# Half_Bridges.net
KiCad netlist of a schematic drawn in Altium Designer
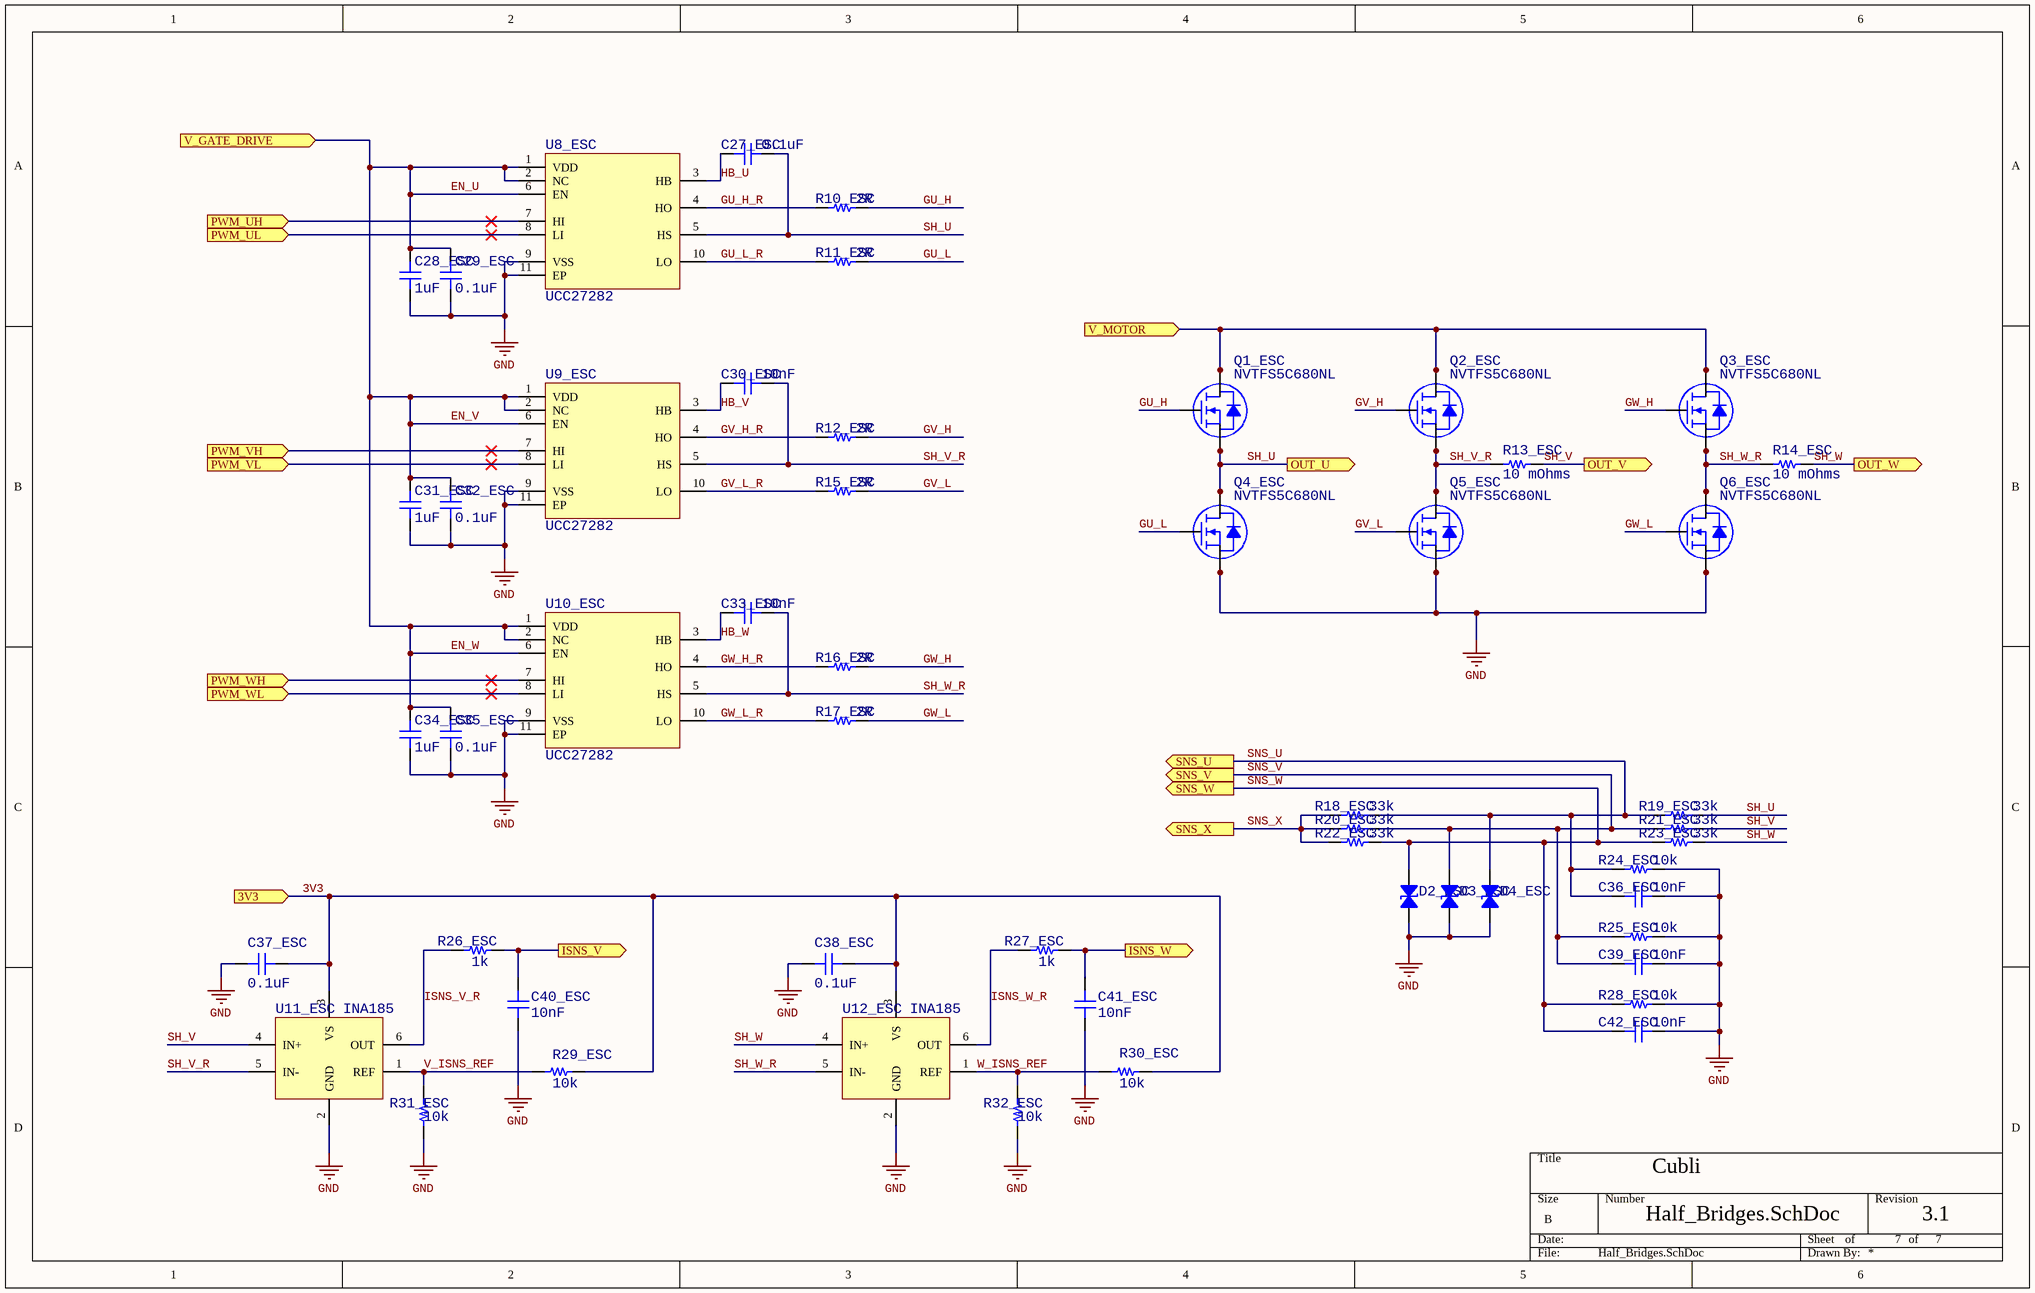
[diagram p0: Half_Bridges.SchDoc]

(export (version "E")
  (design (tool "Eeschema 10.0.6"))
  (components
    (comp (ref "C27_ESC")
      (value "0.1uF")
      (footprint "CAP_0402")
      (description "CAP CER 402")
      (libsource (lib "IC") (part "CAP_0402"))
    )
    (comp (ref "C28_ESC")
      (value "1uF")
      (footprint "CAP_0402")
      (description "CAP CER 402")
      (libsource (lib "IC") (part "CAP_0402"))
    )
    (comp (ref "C29_ESC")
      (value "0.1uF")
      (footprint "CAP_0402")
      (description "CAP CER 402")
      (libsource (lib "IC") (part "CAP_0402"))
    )
    (comp (ref "C30_ESC")
      (value "10nF")
      (footprint "CAP_0402")
      (description "CAP CER 402")
      (libsource (lib "IC") (part "CAP_0402"))
    )
    (comp (ref "C31_ESC")
      (value "1uF")
      (footprint "CAP_0402")
      (description "CAP CER 402")
      (libsource (lib "IC") (part "CAP_0402"))
    )
    (comp (ref "C32_ESC")
      (value "0.1uF")
      (footprint "CAP_0402")
      (description "CAP CER 402")
      (libsource (lib "IC") (part "CAP_0402"))
    )
    (comp (ref "C33_ESC")
      (value "10nF")
      (footprint "CAP_0402")
      (description "CAP CER 402")
      (libsource (lib "IC") (part "CAP_0402"))
    )
    (comp (ref "C34_ESC")
      (value "1uF")
      (footprint "CAP_0402")
      (description "CAP CER 402")
      (libsource (lib "IC") (part "CAP_0402"))
    )
    (comp (ref "C35_ESC")
      (value "0.1uF")
      (footprint "CAP_0402")
      (description "CAP CER 402")
      (libsource (lib "IC") (part "CAP_0402"))
    )
    (comp (ref "C36_ESC")
      (value "10nF")
      (footprint "CAP_0402")
      (description "CAP CER 402")
      (libsource (lib "IC") (part "CAP_0402"))
    )
    (comp (ref "C37_ESC")
      (value "0.1uF")
      (footprint "CAP_0402")
      (description "CAP CER 402")
      (libsource (lib "IC") (part "CAP_0402"))
    )
    (comp (ref "C38_ESC")
      (value "0.1uF")
      (footprint "CAP_0402")
      (description "CAP CER 402")
      (libsource (lib "IC") (part "CAP_0402"))
    )
    (comp (ref "C39_ESC")
      (value "10nF")
      (footprint "CAP_0402")
      (description "CAP CER 402")
      (libsource (lib "IC") (part "CAP_0402"))
    )
    (comp (ref "C40_ESC")
      (value "10nF")
      (footprint "CAP_0402")
      (description "CAP CER 402")
      (libsource (lib "IC") (part "CAP_0402"))
    )
    (comp (ref "C41_ESC")
      (value "10nF")
      (footprint "CAP_0402")
      (description "CAP CER 402")
      (libsource (lib "IC") (part "CAP_0402"))
    )
    (comp (ref "C42_ESC")
      (value "10nF")
      (footprint "CAP_0402")
      (description "CAP CER 402")
      (libsource (lib "IC") (part "CAP_0402"))
    )
    (comp (ref "D2_ESC")
      (value "TVN3V3B1S-DFN1006-2LDG")
      (footprint "0402")
      (description "TVS DIODE 3.3V 14.2PF DFN1006")
      (fields (field (name "MANUFACTURER") "INPAQ Technology Co., Ltd"))
      (libsource (lib "Celestial Altium Library - altium_library") (part "Diode TVS"))
    )
    (comp (ref "D3_ESC")
      (value "TVN3V3B1S-DFN1006-2LDG")
      (footprint "0402")
      (description "TVS DIODE 3.3V 14.2PF DFN1006")
      (fields (field (name "MANUFACTURER") "INPAQ Technology Co., Ltd"))
      (libsource (lib "Celestial Altium Library - altium_library") (part "Diode TVS"))
    )
    (comp (ref "D4_ESC")
      (value "TVN3V3B1S-DFN1006-2LDG")
      (footprint "0402")
      (description "TVS DIODE 3.3V 14.2PF DFN1006")
      (fields (field (name "MANUFACTURER") "INPAQ Technology Co., Ltd"))
      (libsource (lib "Celestial Altium Library - altium_library") (part "Diode TVS"))
    )
    (comp (ref "Q1_ESC")
      (value "NVTFS5C680NL")
      (footprint "NVTFS015N04CTAG")
      (description "N-FET")
      (libsource (lib "IC") (part "NVTFS5C680NL"))
    )
    (comp (ref "Q2_ESC")
      (value "NVTFS5C680NL")
      (footprint "NVTFS015N04CTAG")
      (description "N-FET")
      (libsource (lib "IC") (part "NVTFS5C680NL"))
    )
    (comp (ref "Q3_ESC")
      (value "NVTFS5C680NL")
      (footprint "NVTFS015N04CTAG")
      (description "N-FET")
      (libsource (lib "IC") (part "NVTFS5C680NL"))
    )
    (comp (ref "Q4_ESC")
      (value "NVTFS5C680NL")
      (footprint "NVTFS015N04CTAG")
      (description "N-FET")
      (libsource (lib "IC") (part "NVTFS5C680NL"))
    )
    (comp (ref "Q5_ESC")
      (value "NVTFS5C680NL")
      (footprint "NVTFS015N04CTAG")
      (description "N-FET")
      (libsource (lib "IC") (part "NVTFS5C680NL"))
    )
    (comp (ref "Q6_ESC")
      (value "NVTFS5C680NL")
      (footprint "NVTFS015N04CTAG")
      (description "N-FET")
      (libsource (lib "IC") (part "NVTFS5C680NL"))
    )
    (comp (ref "R10_ESC")
      (value "2R")
      (footprint "RES_0402")
      (description "RES 0402")
      (libsource (lib "IC") (part "RES_0402"))
    )
    (comp (ref "R11_ESC")
      (value "2R")
      (footprint "RES_0402")
      (description "RES 0402")
      (libsource (lib "IC") (part "RES_0402"))
    )
    (comp (ref "R12_ESC")
      (value "2R")
      (footprint "RES_0402")
      (description "RES 0402")
      (libsource (lib "IC") (part "RES_0402"))
    )
    (comp (ref "R13_ESC")
      (value "10 mOhms")
      (footprint "RES 1206_3216")
      (description "RES 0.039 OHM 1% 3/4W 1206")
      (fields (field (name "PART NUMBER") "KRL1632E-M-R039-F-T5") (field (name "MANUFACTURER") "Susumu"))
      (libsource (lib "Celestial Altium Library - altium_library") (part "Resistor"))
    )
    (comp (ref "R14_ESC")
      (value "10 mOhms")
      (footprint "RES 1206_3216")
      (description "RES 0.039 OHM 1% 3/4W 1206")
      (fields (field (name "PART NUMBER") "KRL1632E-M-R039-F-T5") (field (name "MANUFACTURER") "Susumu"))
      (libsource (lib "Celestial Altium Library - altium_library") (part "Resistor"))
    )
    (comp (ref "R15_ESC")
      (value "2R")
      (footprint "RES_0402")
      (description "RES 0402")
      (libsource (lib "IC") (part "RES_0402"))
    )
    (comp (ref "R16_ESC")
      (value "2R")
      (footprint "RES_0402")
      (description "RES 0402")
      (libsource (lib "IC") (part "RES_0402"))
    )
    (comp (ref "R17_ESC")
      (value "2R")
      (footprint "RES_0402")
      (description "RES 0402")
      (libsource (lib "IC") (part "RES_0402"))
    )
    (comp (ref "R18_ESC")
      (value "33k")
      (footprint "RES_0402")
      (description "RES 0402")
      (libsource (lib "IC") (part "RES_0402"))
    )
    (comp (ref "R19_ESC")
      (value "33k")
      (footprint "RES_0402")
      (description "RES 0402")
      (libsource (lib "IC") (part "RES_0402"))
    )
    (comp (ref "R20_ESC")
      (value "33k")
      (footprint "RES_0402")
      (description "RES 0402")
      (libsource (lib "IC") (part "RES_0402"))
    )
    (comp (ref "R21_ESC")
      (value "33k")
      (footprint "RES_0402")
      (description "RES 0402")
      (libsource (lib "IC") (part "RES_0402"))
    )
    (comp (ref "R22_ESC")
      (value "33k")
      (footprint "RES_0402")
      (description "RES 0402")
      (libsource (lib "IC") (part "RES_0402"))
    )
    (comp (ref "R23_ESC")
      (value "33k")
      (footprint "RES_0402")
      (description "RES 0402")
      (libsource (lib "IC") (part "RES_0402"))
    )
    (comp (ref "R24_ESC")
      (value "10k")
      (footprint "RES_0402")
      (description "RES 0402")
      (libsource (lib "IC") (part "RES_0402"))
    )
    (comp (ref "R25_ESC")
      (value "10k")
      (footprint "RES_0402")
      (description "RES 0402")
      (libsource (lib "IC") (part "RES_0402"))
    )
    (comp (ref "R26_ESC")
      (value "1k")
      (footprint "RES_0402")
      (description "RES 0402")
      (libsource (lib "IC") (part "RES_0402"))
    )
    (comp (ref "R27_ESC")
      (value "1k")
      (footprint "RES_0402")
      (description "RES 0402")
      (libsource (lib "IC") (part "RES_0402"))
    )
    (comp (ref "R28_ESC")
      (value "10k")
      (footprint "RES_0402")
      (description "RES 0402")
      (libsource (lib "IC") (part "RES_0402"))
    )
    (comp (ref "R29_ESC")
      (value "10k")
      (footprint "RES_0402")
      (description "RES 0402")
      (libsource (lib "IC") (part "RES_0402"))
    )
    (comp (ref "R30_ESC")
      (value "10k")
      (footprint "RES_0402")
      (description "RES 0402")
      (libsource (lib "IC") (part "RES_0402"))
    )
    (comp (ref "R31_ESC")
      (value "10k")
      (footprint "RES_0402")
      (description "RES 0402")
      (libsource (lib "IC") (part "RES_0402"))
    )
    (comp (ref "R32_ESC")
      (value "10k")
      (footprint "RES_0402")
      (description "RES 0402")
      (libsource (lib "IC") (part "RES_0402"))
    )
    (comp (ref "U8_ESC")
      (value "UCC27282")
      (footprint "VSON-10")
      (description "3-A, 120-V half bridge gate driver with 5-V UVLO, interlock and enable 10-VSON -40 to 125")
      (fields (field (name "MF") "Texas Instruments") (field (name "MP") "UCC27282DRCR"))
      (libsource (lib "IC") (part "UCC27282DRCR"))
    )
    (comp (ref "U9_ESC")
      (value "UCC27282")
      (footprint "VSON-10")
      (description "3-A, 120-V half bridge gate driver with 5-V UVLO, interlock and enable 10-VSON -40 to 125")
      (fields (field (name "MF") "Texas Instruments") (field (name "MP") "UCC27282DRCR"))
      (libsource (lib "IC") (part "UCC27282DRCR"))
    )
    (comp (ref "U10_ESC")
      (value "UCC27282")
      (footprint "VSON-10")
      (description "3-A, 120-V half bridge gate driver with 5-V UVLO, interlock and enable 10-VSON -40 to 125")
      (fields (field (name "MF") "Texas Instruments") (field (name "MP") "UCC27282DRCR"))
      (libsource (lib "IC") (part "UCC27282DRCR"))
    )
    (comp (ref "U11_ESC")
      (value "INA185")
      (footprint "TI SC70-6 DCK")
      (description "INA185A2")
      (libsource (lib "IC") (part "INA185"))
    )
    (comp (ref "U12_ESC")
      (value "INA185")
      (footprint "TI SC70-6 DCK")
      (description "INA185A2")
      (libsource (lib "IC") (part "INA185"))
    )
  )
  (nets
    (net (code "1") (name "/3V3") (class "Default")
      (node (ref "C37_ESC") (pin "1") (pinfunction "1_1") (pintype "passive"))
      (node (ref "C38_ESC") (pin "1") (pinfunction "1_1") (pintype "passive"))
      (node (ref "R29_ESC") (pin "1") (pinfunction "1_1") (pintype "passive"))
      (node (ref "R30_ESC") (pin "1") (pinfunction "1_1") (pintype "passive"))
      (node (ref "U11_ESC") (pin "3") (pinfunction "VS_3") (pintype "passive"))
      (node (ref "U12_ESC") (pin "3") (pinfunction "VS_3") (pintype "passive"))
    )
    (net (code "2") (name "/EN_U") (class "Default")
      (node (ref "C28_ESC") (pin "1") (pinfunction "1_1") (pintype "passive"))
      (node (ref "C29_ESC") (pin "1") (pinfunction "1_1") (pintype "passive"))
      (node (ref "C31_ESC") (pin "1") (pinfunction "1_1") (pintype "passive"))
      (node (ref "C32_ESC") (pin "1") (pinfunction "1_1") (pintype "passive"))
      (node (ref "C34_ESC") (pin "1") (pinfunction "1_1") (pintype "passive"))
      (node (ref "C35_ESC") (pin "1") (pinfunction "1_1") (pintype "passive"))
      (node (ref "U10_ESC") (pin "1") (pinfunction "VDD_1") (pintype "passive"))
      (node (ref "U10_ESC") (pin "2") (pinfunction "NC_2") (pintype "passive"))
      (node (ref "U10_ESC") (pin "6") (pinfunction "EN_6") (pintype "passive"))
      (node (ref "U8_ESC") (pin "1") (pinfunction "VDD_1") (pintype "passive"))
      (node (ref "U8_ESC") (pin "2") (pinfunction "NC_2") (pintype "passive"))
      (node (ref "U8_ESC") (pin "6") (pinfunction "EN_6") (pintype "passive"))
      (node (ref "U9_ESC") (pin "1") (pinfunction "VDD_1") (pintype "passive"))
      (node (ref "U9_ESC") (pin "2") (pinfunction "NC_2") (pintype "passive"))
      (node (ref "U9_ESC") (pin "6") (pinfunction "EN_6") (pintype "passive"))
    )
    (net (code "3") (name "/GU_H") (class "Default")
      (node (ref "Q1_ESC") (pin "4") (pinfunction "G_4") (pintype "passive"))
      (node (ref "R10_ESC") (pin "2") (pinfunction "2_2") (pintype "passive"))
    )
    (net (code "4") (name "/GU_H_R") (class "Default")
      (node (ref "R10_ESC") (pin "1") (pinfunction "1_1") (pintype "passive"))
      (node (ref "U8_ESC") (pin "4") (pinfunction "HO_4") (pintype "passive"))
    )
    (net (code "5") (name "/GU_L") (class "Default")
      (node (ref "Q4_ESC") (pin "4") (pinfunction "G_4") (pintype "passive"))
      (node (ref "R11_ESC") (pin "2") (pinfunction "2_2") (pintype "passive"))
    )
    (net (code "6") (name "/GU_L_R") (class "Default")
      (node (ref "R11_ESC") (pin "1") (pinfunction "1_1") (pintype "passive"))
      (node (ref "U8_ESC") (pin "10") (pinfunction "LO_10") (pintype "passive"))
    )
    (net (code "7") (name "/GV_H") (class "Default")
      (node (ref "Q2_ESC") (pin "4") (pinfunction "G_4") (pintype "passive"))
      (node (ref "R12_ESC") (pin "2") (pinfunction "2_2") (pintype "passive"))
    )
    (net (code "8") (name "/GV_H_R") (class "Default")
      (node (ref "R12_ESC") (pin "1") (pinfunction "1_1") (pintype "passive"))
      (node (ref "U9_ESC") (pin "4") (pinfunction "HO_4") (pintype "passive"))
    )
    (net (code "9") (name "/GV_L") (class "Default")
      (node (ref "Q5_ESC") (pin "4") (pinfunction "G_4") (pintype "passive"))
      (node (ref "R15_ESC") (pin "2") (pinfunction "2_2") (pintype "passive"))
    )
    (net (code "10") (name "/GV_L_R") (class "Default")
      (node (ref "R15_ESC") (pin "1") (pinfunction "1_1") (pintype "passive"))
      (node (ref "U9_ESC") (pin "10") (pinfunction "LO_10") (pintype "passive"))
    )
    (net (code "11") (name "/GW_H") (class "Default")
      (node (ref "Q3_ESC") (pin "4") (pinfunction "G_4") (pintype "passive"))
      (node (ref "R16_ESC") (pin "2") (pinfunction "2_2") (pintype "passive"))
    )
    (net (code "12") (name "/GW_H_R") (class "Default")
      (node (ref "R16_ESC") (pin "1") (pinfunction "1_1") (pintype "passive"))
      (node (ref "U10_ESC") (pin "4") (pinfunction "HO_4") (pintype "passive"))
    )
    (net (code "13") (name "/GW_L") (class "Default")
      (node (ref "Q6_ESC") (pin "4") (pinfunction "G_4") (pintype "passive"))
      (node (ref "R17_ESC") (pin "2") (pinfunction "2_2") (pintype "passive"))
    )
    (net (code "14") (name "/GW_L_R") (class "Default")
      (node (ref "R17_ESC") (pin "1") (pinfunction "1_1") (pintype "passive"))
      (node (ref "U10_ESC") (pin "10") (pinfunction "LO_10") (pintype "passive"))
    )
    (net (code "15") (name "/HB_U") (class "Default")
      (node (ref "C27_ESC") (pin "2") (pinfunction "2_2") (pintype "passive"))
      (node (ref "U8_ESC") (pin "3") (pinfunction "HB_3") (pintype "passive"))
    )
    (net (code "16") (name "/HB_V") (class "Default")
      (node (ref "C30_ESC") (pin "2") (pinfunction "2_2") (pintype "passive"))
      (node (ref "U9_ESC") (pin "3") (pinfunction "HB_3") (pintype "passive"))
    )
    (net (code "17") (name "/HB_W") (class "Default")
      (node (ref "C33_ESC") (pin "2") (pinfunction "2_2") (pintype "passive"))
      (node (ref "U10_ESC") (pin "3") (pinfunction "HB_3") (pintype "passive"))
    )
    (net (code "18") (name "/ISNS_V") (class "Default")
      (node (ref "C40_ESC") (pin "1") (pinfunction "1_1") (pintype "passive"))
      (node (ref "R26_ESC") (pin "1") (pinfunction "1_1") (pintype "passive"))
    )
    (net (code "19") (name "/ISNS_V_R") (class "Default")
      (node (ref "R26_ESC") (pin "2") (pinfunction "2_2") (pintype "passive"))
      (node (ref "U11_ESC") (pin "6") (pinfunction "OUT_6") (pintype "passive"))
    )
    (net (code "20") (name "/ISNS_W") (class "Default")
      (node (ref "C41_ESC") (pin "1") (pinfunction "1_1") (pintype "passive"))
      (node (ref "R27_ESC") (pin "1") (pinfunction "1_1") (pintype "passive"))
    )
    (net (code "21") (name "/ISNS_W_R") (class "Default")
      (node (ref "R27_ESC") (pin "2") (pinfunction "2_2") (pintype "passive"))
      (node (ref "U12_ESC") (pin "6") (pinfunction "OUT_6") (pintype "passive"))
    )
    (net (code "22") (name "/PWM_UH") (class "Default")
      (node (ref "U8_ESC") (pin "7") (pinfunction "HI_7") (pintype "passive"))
    )
    (net (code "23") (name "/PWM_UL") (class "Default")
      (node (ref "U8_ESC") (pin "8") (pinfunction "LI_8") (pintype "passive"))
    )
    (net (code "24") (name "/PWM_VH") (class "Default")
      (node (ref "U9_ESC") (pin "7") (pinfunction "HI_7") (pintype "passive"))
    )
    (net (code "25") (name "/PWM_VL") (class "Default")
      (node (ref "U9_ESC") (pin "8") (pinfunction "LI_8") (pintype "passive"))
    )
    (net (code "26") (name "/PWM_WH") (class "Default")
      (node (ref "U10_ESC") (pin "7") (pinfunction "HI_7") (pintype "passive"))
    )
    (net (code "27") (name "/PWM_WL") (class "Default")
      (node (ref "U10_ESC") (pin "8") (pinfunction "LI_8") (pintype "passive"))
    )
    (net (code "28") (name "/SH_U") (class "Default")
      (node (ref "C27_ESC") (pin "1") (pinfunction "1_1") (pintype "passive"))
      (node (ref "Q1_ESC") (pin "1") (pinfunction "S_1") (pintype "passive"))
      (node (ref "Q1_ESC") (pin "2") (pinfunction "S_2") (pintype "passive"))
      (node (ref "Q1_ESC") (pin "3") (pinfunction "S_3") (pintype "passive"))
      (node (ref "Q4_ESC") (pin "5") (pinfunction "D_5") (pintype "passive"))
      (node (ref "Q4_ESC") (pin "6") (pinfunction "D_6") (pintype "passive"))
      (node (ref "Q4_ESC") (pin "7") (pinfunction "D_7") (pintype "passive"))
      (node (ref "Q4_ESC") (pin "8") (pinfunction "D_8") (pintype "passive"))
      (node (ref "R19_ESC") (pin "1") (pinfunction "1_1") (pintype "passive"))
      (node (ref "U8_ESC") (pin "5") (pinfunction "HS_5") (pintype "passive"))
    )
    (net (code "29") (name "/SH_V") (class "Default")
      (node (ref "R13_ESC") (pin "2") (pinfunction "2_2") (pintype "passive"))
      (node (ref "R21_ESC") (pin "1") (pinfunction "1_1") (pintype "passive"))
      (node (ref "U11_ESC") (pin "4") (pinfunction "IN+_4") (pintype "passive"))
    )
    (net (code "30") (name "/SH_V_R") (class "Default")
      (node (ref "C30_ESC") (pin "1") (pinfunction "1_1") (pintype "passive"))
      (node (ref "Q2_ESC") (pin "1") (pinfunction "S_1") (pintype "passive"))
      (node (ref "Q2_ESC") (pin "2") (pinfunction "S_2") (pintype "passive"))
      (node (ref "Q2_ESC") (pin "3") (pinfunction "S_3") (pintype "passive"))
      (node (ref "Q5_ESC") (pin "5") (pinfunction "D_5") (pintype "passive"))
      (node (ref "Q5_ESC") (pin "6") (pinfunction "D_6") (pintype "passive"))
      (node (ref "Q5_ESC") (pin "7") (pinfunction "D_7") (pintype "passive"))
      (node (ref "Q5_ESC") (pin "8") (pinfunction "D_8") (pintype "passive"))
      (node (ref "R13_ESC") (pin "1") (pinfunction "1_1") (pintype "passive"))
      (node (ref "U11_ESC") (pin "5") (pinfunction "IN-_5") (pintype "passive"))
      (node (ref "U9_ESC") (pin "5") (pinfunction "HS_5") (pintype "passive"))
    )
    (net (code "31") (name "/SH_W") (class "Default")
      (node (ref "R14_ESC") (pin "2") (pinfunction "2_2") (pintype "passive"))
      (node (ref "R23_ESC") (pin "1") (pinfunction "1_1") (pintype "passive"))
      (node (ref "U12_ESC") (pin "4") (pinfunction "IN+_4") (pintype "passive"))
    )
    (net (code "32") (name "/SH_W_R") (class "Default")
      (node (ref "C33_ESC") (pin "1") (pinfunction "1_1") (pintype "passive"))
      (node (ref "Q3_ESC") (pin "1") (pinfunction "S_1") (pintype "passive"))
      (node (ref "Q3_ESC") (pin "2") (pinfunction "S_2") (pintype "passive"))
      (node (ref "Q3_ESC") (pin "3") (pinfunction "S_3") (pintype "passive"))
      (node (ref "Q6_ESC") (pin "5") (pinfunction "D_5") (pintype "passive"))
      (node (ref "Q6_ESC") (pin "6") (pinfunction "D_6") (pintype "passive"))
      (node (ref "Q6_ESC") (pin "7") (pinfunction "D_7") (pintype "passive"))
      (node (ref "Q6_ESC") (pin "8") (pinfunction "D_8") (pintype "passive"))
      (node (ref "R14_ESC") (pin "1") (pinfunction "1_1") (pintype "passive"))
      (node (ref "U10_ESC") (pin "5") (pinfunction "HS_5") (pintype "passive"))
      (node (ref "U12_ESC") (pin "5") (pinfunction "IN-_5") (pintype "passive"))
    )
    (net (code "33") (name "/SNS_U") (class "Default")
      (node (ref "C36_ESC") (pin "2") (pinfunction "2_2") (pintype "passive"))
      (node (ref "D4_ESC") (pin "2") (pinfunction "2_2") (pintype "passive"))
      (node (ref "R18_ESC") (pin "1") (pinfunction "1_1") (pintype "passive"))
      (node (ref "R19_ESC") (pin "2") (pinfunction "2_2") (pintype "passive"))
      (node (ref "R24_ESC") (pin "1") (pinfunction "1_1") (pintype "passive"))
    )
    (net (code "34") (name "/SNS_V") (class "Default")
      (node (ref "C39_ESC") (pin "2") (pinfunction "2_2") (pintype "passive"))
      (node (ref "D3_ESC") (pin "2") (pinfunction "2_2") (pintype "passive"))
      (node (ref "R20_ESC") (pin "1") (pinfunction "1_1") (pintype "passive"))
      (node (ref "R21_ESC") (pin "2") (pinfunction "2_2") (pintype "passive"))
      (node (ref "R25_ESC") (pin "1") (pinfunction "1_1") (pintype "passive"))
    )
    (net (code "35") (name "/SNS_W") (class "Default")
      (node (ref "C42_ESC") (pin "2") (pinfunction "2_2") (pintype "passive"))
      (node (ref "D2_ESC") (pin "2") (pinfunction "2_2") (pintype "passive"))
      (node (ref "R22_ESC") (pin "1") (pinfunction "1_1") (pintype "passive"))
      (node (ref "R23_ESC") (pin "2") (pinfunction "2_2") (pintype "passive"))
      (node (ref "R28_ESC") (pin "1") (pinfunction "1_1") (pintype "passive"))
    )
    (net (code "36") (name "/SNS_X") (class "Default")
      (node (ref "R18_ESC") (pin "2") (pinfunction "2_2") (pintype "passive"))
      (node (ref "R20_ESC") (pin "2") (pinfunction "2_2") (pintype "passive"))
      (node (ref "R22_ESC") (pin "2") (pinfunction "2_2") (pintype "passive"))
    )
    (net (code "37") (name "/V_ISNS_REF") (class "Default")
      (node (ref "R29_ESC") (pin "2") (pinfunction "2_2") (pintype "passive"))
      (node (ref "R31_ESC") (pin "1") (pinfunction "1_1") (pintype "passive"))
      (node (ref "U11_ESC") (pin "1") (pinfunction "REF_1") (pintype "passive"))
    )
    (net (code "38") (name "/V_MOTOR") (class "Default")
      (node (ref "Q1_ESC") (pin "5") (pinfunction "D_5") (pintype "passive"))
      (node (ref "Q1_ESC") (pin "6") (pinfunction "D_6") (pintype "passive"))
      (node (ref "Q1_ESC") (pin "7") (pinfunction "D_7") (pintype "passive"))
      (node (ref "Q1_ESC") (pin "8") (pinfunction "D_8") (pintype "passive"))
      (node (ref "Q2_ESC") (pin "5") (pinfunction "D_5") (pintype "passive"))
      (node (ref "Q2_ESC") (pin "6") (pinfunction "D_6") (pintype "passive"))
      (node (ref "Q2_ESC") (pin "7") (pinfunction "D_7") (pintype "passive"))
      (node (ref "Q2_ESC") (pin "8") (pinfunction "D_8") (pintype "passive"))
      (node (ref "Q3_ESC") (pin "5") (pinfunction "D_5") (pintype "passive"))
      (node (ref "Q3_ESC") (pin "6") (pinfunction "D_6") (pintype "passive"))
      (node (ref "Q3_ESC") (pin "7") (pinfunction "D_7") (pintype "passive"))
      (node (ref "Q3_ESC") (pin "8") (pinfunction "D_8") (pintype "passive"))
    )
    (net (code "39") (name "/W_ISNS_REF") (class "Default")
      (node (ref "R30_ESC") (pin "2") (pinfunction "2_2") (pintype "passive"))
      (node (ref "R32_ESC") (pin "1") (pinfunction "1_1") (pintype "passive"))
      (node (ref "U12_ESC") (pin "1") (pinfunction "REF_1") (pintype "passive"))
    )
    (net (code "40") (name "GND") (class "Default")
      (node (ref "C28_ESC") (pin "2") (pinfunction "2_2") (pintype "passive"))
      (node (ref "C29_ESC") (pin "2") (pinfunction "2_2") (pintype "passive"))
      (node (ref "C31_ESC") (pin "2") (pinfunction "2_2") (pintype "passive"))
      (node (ref "C32_ESC") (pin "2") (pinfunction "2_2") (pintype "passive"))
      (node (ref "C34_ESC") (pin "2") (pinfunction "2_2") (pintype "passive"))
      (node (ref "C35_ESC") (pin "2") (pinfunction "2_2") (pintype "passive"))
      (node (ref "C36_ESC") (pin "1") (pinfunction "1_1") (pintype "passive"))
      (node (ref "C37_ESC") (pin "2") (pinfunction "2_2") (pintype "passive"))
      (node (ref "C38_ESC") (pin "2") (pinfunction "2_2") (pintype "passive"))
      (node (ref "C39_ESC") (pin "1") (pinfunction "1_1") (pintype "passive"))
      (node (ref "C40_ESC") (pin "2") (pinfunction "2_2") (pintype "passive"))
      (node (ref "C41_ESC") (pin "2") (pinfunction "2_2") (pintype "passive"))
      (node (ref "C42_ESC") (pin "1") (pinfunction "1_1") (pintype "passive"))
      (node (ref "D2_ESC") (pin "1") (pinfunction "1_1") (pintype "passive"))
      (node (ref "D3_ESC") (pin "1") (pinfunction "1_1") (pintype "passive"))
      (node (ref "D4_ESC") (pin "1") (pinfunction "1_1") (pintype "passive"))
      (node (ref "Q4_ESC") (pin "1") (pinfunction "S_1") (pintype "passive"))
      (node (ref "Q4_ESC") (pin "2") (pinfunction "S_2") (pintype "passive"))
      (node (ref "Q4_ESC") (pin "3") (pinfunction "S_3") (pintype "passive"))
      (node (ref "Q5_ESC") (pin "1") (pinfunction "S_1") (pintype "passive"))
      (node (ref "Q5_ESC") (pin "2") (pinfunction "S_2") (pintype "passive"))
      (node (ref "Q5_ESC") (pin "3") (pinfunction "S_3") (pintype "passive"))
      (node (ref "Q6_ESC") (pin "1") (pinfunction "S_1") (pintype "passive"))
      (node (ref "Q6_ESC") (pin "2") (pinfunction "S_2") (pintype "passive"))
      (node (ref "Q6_ESC") (pin "3") (pinfunction "S_3") (pintype "passive"))
      (node (ref "R24_ESC") (pin "2") (pinfunction "2_2") (pintype "passive"))
      (node (ref "R25_ESC") (pin "2") (pinfunction "2_2") (pintype "passive"))
      (node (ref "R28_ESC") (pin "2") (pinfunction "2_2") (pintype "passive"))
      (node (ref "R31_ESC") (pin "2") (pinfunction "2_2") (pintype "passive"))
      (node (ref "R32_ESC") (pin "2") (pinfunction "2_2") (pintype "passive"))
      (node (ref "U10_ESC") (pin "11") (pinfunction "EP_11") (pintype "passive"))
      (node (ref "U10_ESC") (pin "9") (pinfunction "VSS_9") (pintype "passive"))
      (node (ref "U11_ESC") (pin "2") (pinfunction "GND_2") (pintype "passive"))
      (node (ref "U12_ESC") (pin "2") (pinfunction "GND_2") (pintype "passive"))
      (node (ref "U8_ESC") (pin "11") (pinfunction "EP_11") (pintype "passive"))
      (node (ref "U8_ESC") (pin "9") (pinfunction "VSS_9") (pintype "passive"))
      (node (ref "U9_ESC") (pin "11") (pinfunction "EP_11") (pintype "passive"))
      (node (ref "U9_ESC") (pin "9") (pinfunction "VSS_9") (pintype "passive"))
    )
  )
)
